# MP2236.net
KiCad netlist of a schematic drawn in EasyEDA Pro
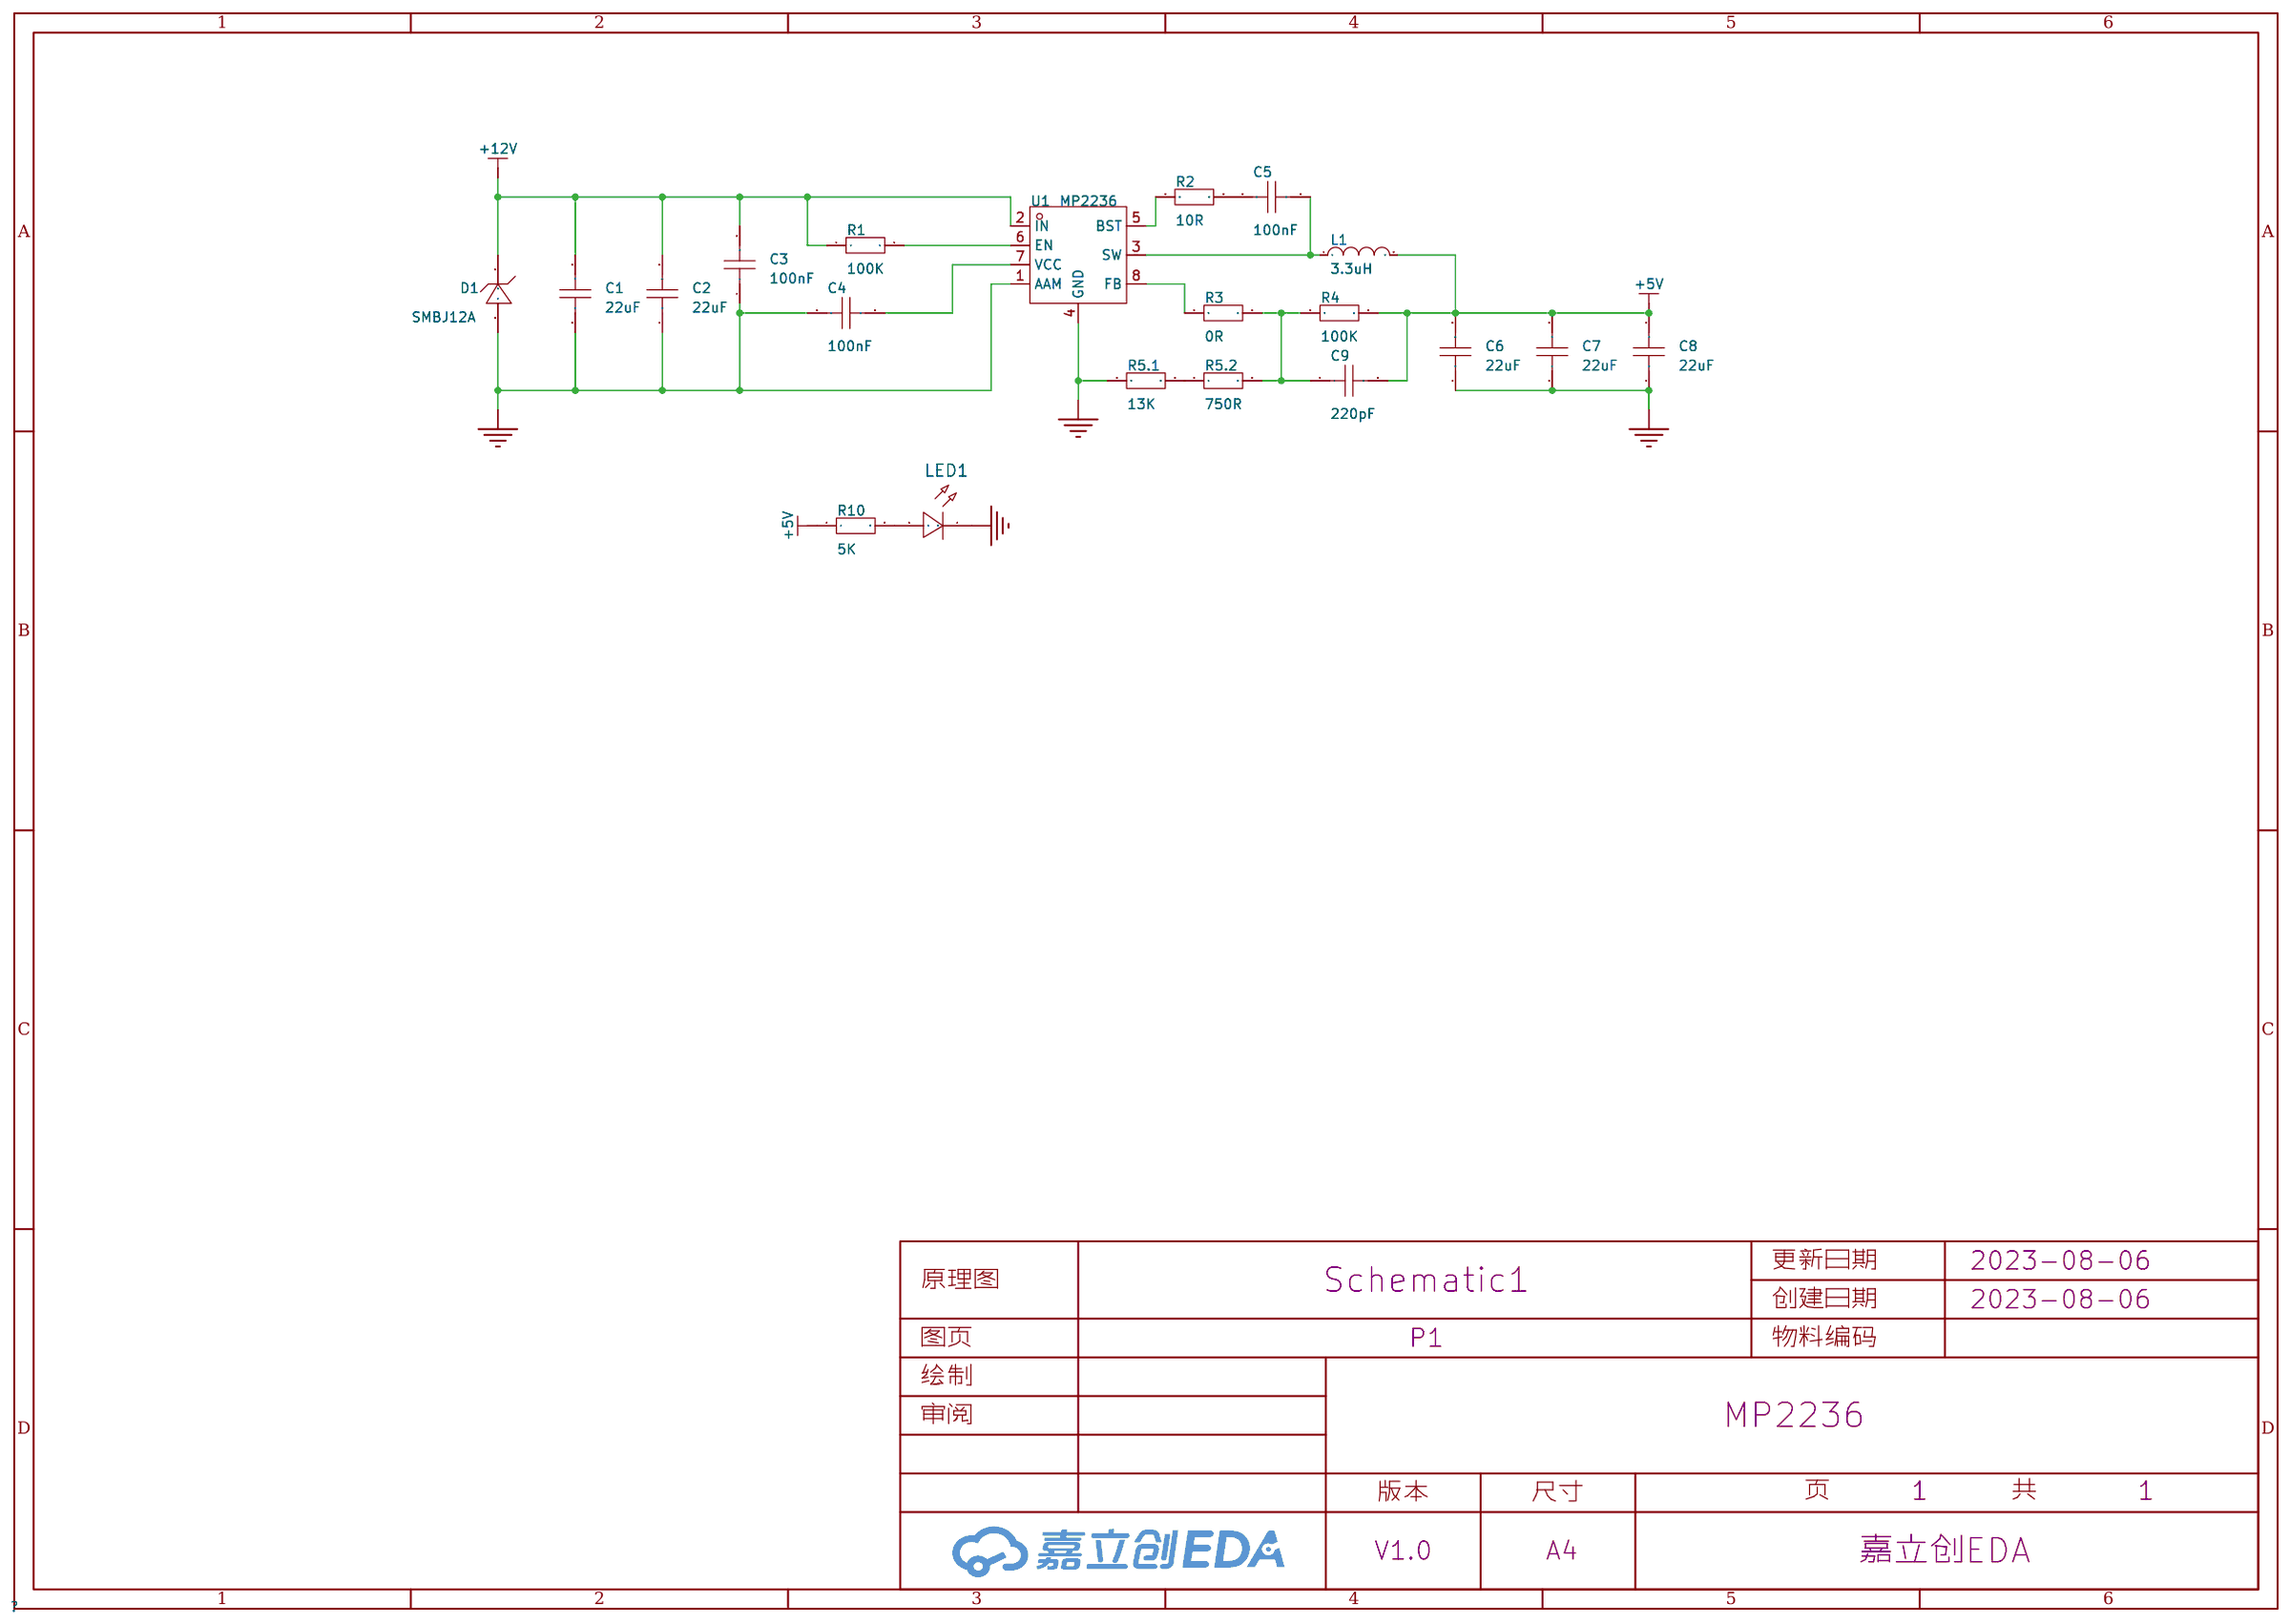
[diagram p0: schematic sheet]

(export (version "E")
  (design (tool "Eeschema 10.0.6"))
  (components
    (comp (ref "C1")
      (value "22uF")
      (footprint "easyedapro:C1206")
      (libsource (lib "easyedapro") (part "CapAcitance"))
    )
    (comp (ref "C2")
      (value "22uF")
      (footprint "easyedapro:C1206")
      (libsource (lib "easyedapro") (part "CapAcitance"))
    )
    (comp (ref "C3")
      (value "100nF")
      (footprint "easyedapro:C1206")
      (libsource (lib "easyedapro") (part "CapAcitance"))
    )
    (comp (ref "C4")
      (value "100nF")
      (footprint "easyedapro:C1206")
      (libsource (lib "easyedapro") (part "CapAcitance"))
    )
    (comp (ref "C5")
      (value "100nF")
      (footprint "easyedapro:C1206")
      (libsource (lib "easyedapro") (part "CapAcitance"))
    )
    (comp (ref "C6")
      (value "22uF")
      (footprint "easyedapro:C1206")
      (libsource (lib "easyedapro") (part "CapAcitance"))
    )
    (comp (ref "C7")
      (value "22uF")
      (footprint "easyedapro:C1206")
      (libsource (lib "easyedapro") (part "CapAcitance"))
    )
    (comp (ref "C8")
      (value "22uF")
      (footprint "easyedapro:C1206")
      (libsource (lib "easyedapro") (part "CapAcitance"))
    )
    (comp (ref "C9")
      (value "220pF")
      (footprint "easyedapro:C1206")
      (libsource (lib "easyedapro") (part "CapAcitance"))
    )
    (comp (ref "D1")
      (value "SMBJ12A")
      (footprint "easyedapro:SMB_L4.6-W3.6-LS5.3-RD")
      (description "极性:Unidirectional;峰值脉冲电流（10/1000us）:30.2A;箝位电压:19.9V;击穿电压（最小值）:13.3V;反向关断电压（典型值）:12V;")
      (libsource (lib "easyedapro") (part "SMBJ12A-C127552"))
    )
    (comp (ref "L1")
      (value "3.3uH")
      (footprint "easyedapro:IND-SMD_L7.3-W6.6")
      (description "电感值:2.2uH;精度:±20%;额定电流:8A;饱和电流(Isat):12A;")
      (fields (field (name "Manufacturer Part") "MCS0630-2R2MPY1") (field (name "Manufacturer") "PSA(信昌电陶)"))
      (libsource (lib "easyedapro") (part "MCS0630-2R2MPY1"))
    )
    (comp (ref "LED1")
      (value "~")
      (footprint "easyedapro:LED_0603")
      (libsource (lib "easyedapro") (part "LED_R"))
    )
    (comp (ref "R1") (value "100K") (footprint "easyedapro:R0603") (libsource (lib "easyedapro") (part "电阻")))
    (comp (ref "R2") (value "10R") (footprint "easyedapro:R0603") (libsource (lib "easyedapro") (part "电阻")))
    (comp (ref "R3") (value "0R") (footprint "easyedapro:R0603") (libsource (lib "easyedapro") (part "电阻")))
    (comp (ref "R4") (value "100K") (footprint "easyedapro:R0603") (libsource (lib "easyedapro") (part "电阻")))
    (comp (ref "R5.1")
      (value "13K")
      (footprint "easyedapro:R0603")
      (libsource (lib "easyedapro") (part "电阻"))
    )
    (comp (ref "R5.2")
      (value "750R")
      (footprint "easyedapro:R0603")
      (libsource (lib "easyedapro") (part "电阻"))
    )
    (comp (ref "R10") (value "5K") (footprint "easyedapro:R0603") (libsource (lib "easyedapro") (part "电阻")))
    (comp (ref "U1")
      (value "MP2236")
      (footprint "easyedapro:TSOT-23-8_L2.9-W1.6-P0.65-LS2.8-BL")
      (libsource (lib "easyedapro") (part "MP2315SGJ-Z"))
    )
  )
  (nets
    (net (code "1") (name "+5V") (class "Default")
      (node (ref "C6") (pin "2") (pinfunction "2_2") (pintype "input"))
      (node (ref "C7") (pin "2") (pinfunction "2_2") (pintype "input"))
      (node (ref "C8") (pin "2") (pinfunction "2_2") (pintype "input"))
      (node (ref "C9") (pin "2") (pinfunction "2_2") (pintype "input"))
      (node (ref "L1") (pin "2") (pinfunction "2_2") (pintype "input"))
      (node (ref "R10") (pin "1") (pinfunction "1_1") (pintype "input"))
      (node (ref "R4") (pin "2") (pinfunction "2_2") (pintype "input"))
    )
    (net (code "2") (name "+12V") (class "Default")
      (node (ref "C1") (pin "2") (pinfunction "2_2") (pintype "input"))
      (node (ref "C2") (pin "2") (pinfunction "2_2") (pintype "input"))
      (node (ref "C3") (pin "2") (pinfunction "2_2") (pintype "input"))
      (node (ref "D1") (pin "1") (pinfunction "C_1") (pintype "input"))
      (node (ref "R1") (pin "1") (pinfunction "1_1") (pintype "input"))
      (node (ref "U1") (pin "2") (pinfunction "IN_2") (pintype "input"))
    )
    (net (code "3") (name "GND") (class "Default")
      (node (ref "C1") (pin "1") (pinfunction "1_1") (pintype "input"))
      (node (ref "C2") (pin "1") (pinfunction "1_1") (pintype "input"))
      (node (ref "C3") (pin "1") (pinfunction "1_1") (pintype "input"))
      (node (ref "C4") (pin "1") (pinfunction "1_1") (pintype "input"))
      (node (ref "C6") (pin "1") (pinfunction "1_1") (pintype "input"))
      (node (ref "C7") (pin "1") (pinfunction "1_1") (pintype "input"))
      (node (ref "C8") (pin "1") (pinfunction "1_1") (pintype "input"))
      (node (ref "D1") (pin "2") (pinfunction "A_2") (pintype "input"))
      (node (ref "LED1") (pin "1") (pinfunction "C_1") (pintype "input"))
      (node (ref "R5.1") (pin "1") (pinfunction "1_1") (pintype "input"))
      (node (ref "U1") (pin "1") (pinfunction "AAM_1") (pintype "input"))
      (node (ref "U1") (pin "4") (pinfunction "GND_4") (pintype "input"))
    )
    (net (code "4") (name "Net-(C5-Pad1)") (class "Default")
      (node (ref "C5") (pin "1") (pinfunction "1_1") (pintype "input"))
      (node (ref "R2") (pin "2") (pinfunction "2_2") (pintype "input"))
    )
    (net (code "5") (name "Net-(C9-Pad1)") (class "Default")
      (node (ref "C9") (pin "1") (pinfunction "1_1") (pintype "input"))
      (node (ref "R3") (pin "2") (pinfunction "2_2") (pintype "input"))
      (node (ref "R4") (pin "1") (pinfunction "1_1") (pintype "input"))
      (node (ref "R5.2") (pin "2") (pinfunction "2_2") (pintype "input"))
    )
    (net (code "6") (name "Net-(LED1-A)") (class "Default")
      (node (ref "LED1") (pin "2") (pinfunction "A_2") (pintype "input"))
      (node (ref "R10") (pin "2") (pinfunction "2_2") (pintype "input"))
    )
    (net (code "7") (name "Net-(R5.1-Pad2)") (class "Default")
      (node (ref "R5.1") (pin "2") (pinfunction "2_2") (pintype "input"))
      (node (ref "R5.2") (pin "1") (pinfunction "1_1") (pintype "input"))
    )
    (net (code "8") (name "Net-(U1-BST)") (class "Default")
      (node (ref "R2") (pin "1") (pinfunction "1_1") (pintype "input"))
      (node (ref "U1") (pin "5") (pinfunction "BST_5") (pintype "input"))
    )
    (net (code "9") (name "Net-(U1-EN)") (class "Default")
      (node (ref "R1") (pin "2") (pinfunction "2_2") (pintype "input"))
      (node (ref "U1") (pin "6") (pinfunction "EN_6") (pintype "input"))
    )
    (net (code "10") (name "Net-(U1-FB)") (class "Default")
      (node (ref "R3") (pin "1") (pinfunction "1_1") (pintype "input"))
      (node (ref "U1") (pin "8") (pinfunction "FB_8") (pintype "input"))
    )
    (net (code "11") (name "Net-(U1-SW)") (class "Default")
      (node (ref "C5") (pin "2") (pinfunction "2_2") (pintype "input"))
      (node (ref "L1") (pin "1") (pinfunction "1_1") (pintype "input"))
      (node (ref "U1") (pin "3") (pinfunction "SW_3") (pintype "input"))
    )
    (net (code "12") (name "Net-(U1-VCC)") (class "Default")
      (node (ref "C4") (pin "2") (pinfunction "2_2") (pintype "input"))
      (node (ref "U1") (pin "7") (pinfunction "VCC_7") (pintype "input"))
    )
  )
)
